# SchemaSplit_2_into_1_1.net
KiCad netlist of a schematic drawn in Altium Designer
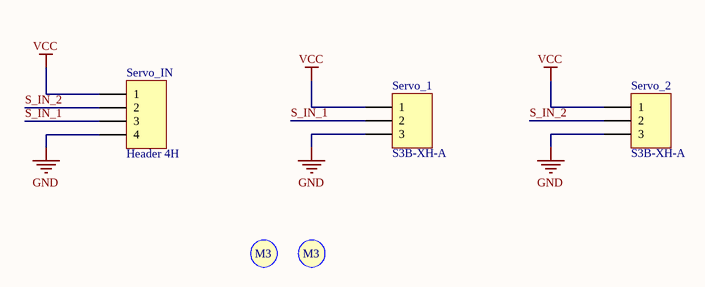
[diagram p0: SchemaSplit_2_into_1_1.SchDoc]

(export (version "E")
  (design (tool "Eeschema 10.0.6"))
  (components
    (comp (ref "S1")
      (value "Screw M3")
      (footprint "Screw M3")
      (libsource (lib "Robot_2019") (part "Screw M3"))
    )
    (comp (ref "S2")
      (value "Screw M3")
      (footprint "Screw M3")
      (libsource (lib "Robot_2019") (part "Screw M3"))
    )
    (comp (ref "Servo_1")
      (value "S3B-XH-A")
      (footprint "S3B-XH-A")
      (description "Header, 3-Pin, Right Angle")
      (fields (field (name "PUBLISHER") "Altium Limited"))
      (libsource (lib "Miscellaneous Connectors") (part "Header 3H"))
    )
    (comp (ref "Servo_2")
      (value "S3B-XH-A")
      (footprint "S3B-XH-A")
      (description "Header, 3-Pin, Right Angle")
      (fields (field (name "PUBLISHER") "Altium Limited"))
      (libsource (lib "Miscellaneous Connectors") (part "Header 3H"))
    )
    (comp (ref "Servo_IN")
      (value "Header 4H")
      (footprint "S4B-XH-A")
      (description "Header, 4-Pin, Right Angle")
      (fields (field (name "PUBLISHER") "Altium Limited"))
      (libsource (lib "Miscellaneous Connectors") (part "Header 4H"))
    )
  )
  (nets
    (net (code "1") (name "/S_IN_1") (class "Default")
      (node (ref "Servo_1") (pin "2") (pinfunction "2_2") (pintype "passive"))
      (node (ref "Servo_IN") (pin "3") (pinfunction "3_3") (pintype "passive"))
    )
    (net (code "2") (name "/S_IN_2") (class "Default")
      (node (ref "Servo_2") (pin "2") (pinfunction "2_2") (pintype "passive"))
      (node (ref "Servo_IN") (pin "2") (pinfunction "2_2") (pintype "passive"))
    )
    (net (code "3") (name "GND") (class "Default")
      (node (ref "Servo_1") (pin "3") (pinfunction "3_3") (pintype "passive"))
      (node (ref "Servo_2") (pin "3") (pinfunction "3_3") (pintype "passive"))
      (node (ref "Servo_IN") (pin "4") (pinfunction "4_4") (pintype "passive"))
    )
    (net (code "4") (name "VCC") (class "Default")
      (node (ref "Servo_1") (pin "1") (pinfunction "1_1") (pintype "passive"))
      (node (ref "Servo_2") (pin "1") (pinfunction "1_1") (pintype "passive"))
      (node (ref "Servo_IN") (pin "1") (pinfunction "1_1") (pintype "passive"))
    )
  )
)
